# PowerPump_Circuitry.net
KiCad netlist of a schematic drawn in Altium Designer
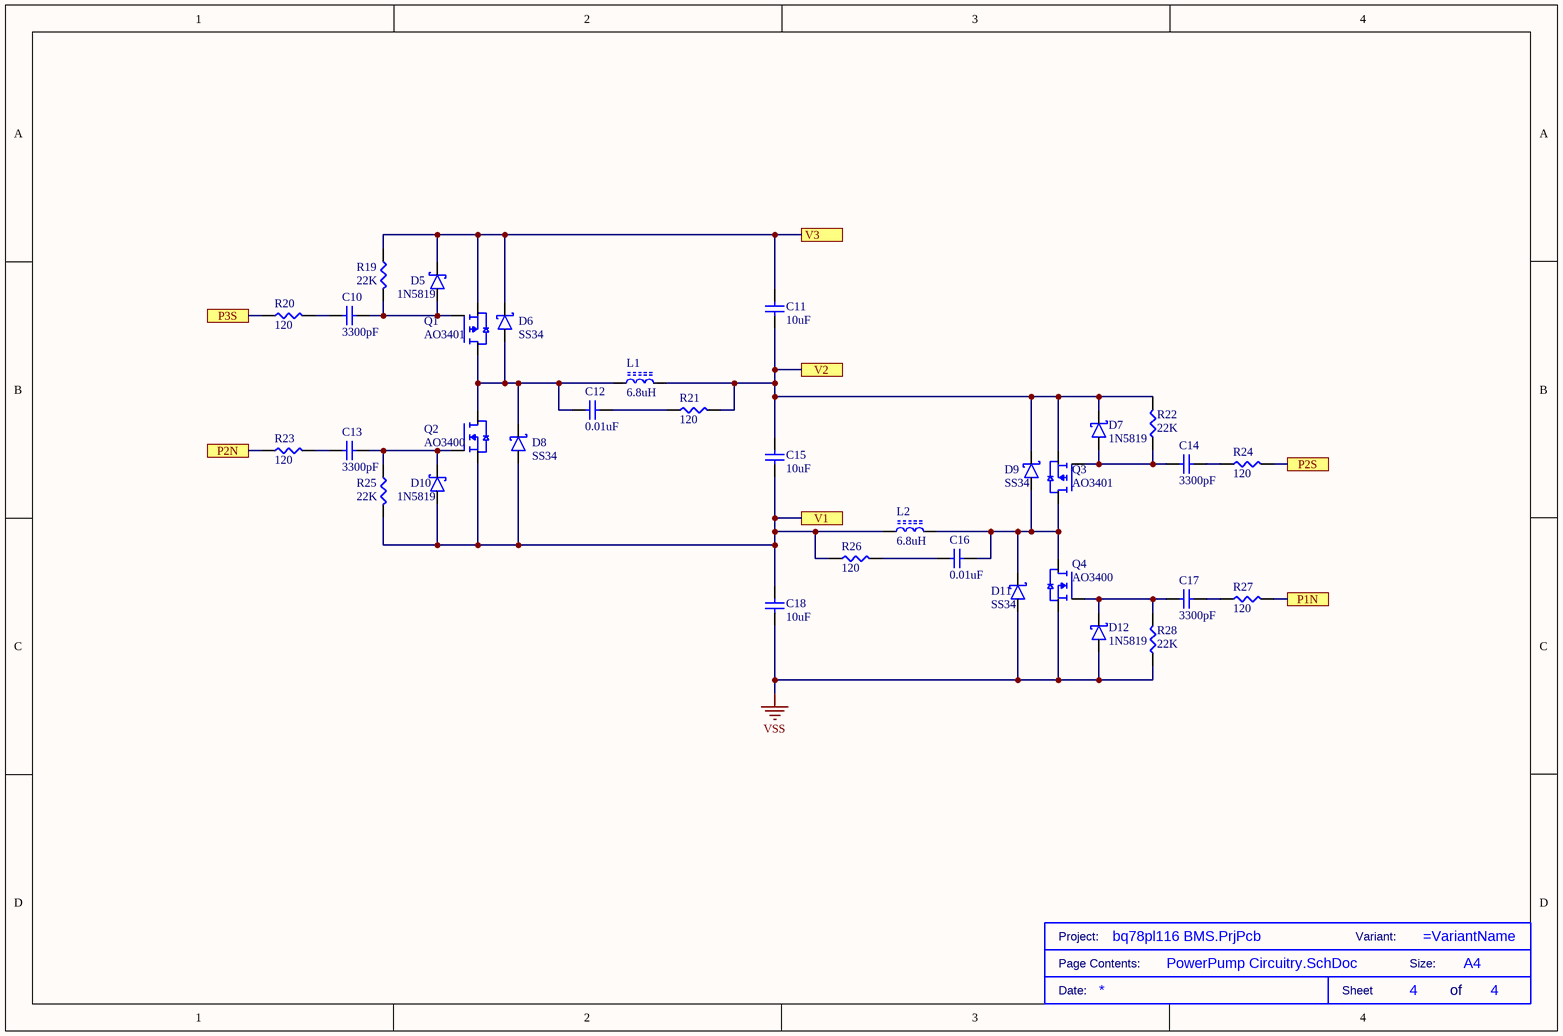
[diagram p0: PowerPump Circuitry.SchDoc]

(export (version "E")
  (design (tool "Eeschema 10.0.6"))
  (components
    (comp (ref "C10")
      (value "3300pF")
      (footprint "C0805")
      (description "Cap Ceramic 0.0033uF 50V X7R 10% SMD 0805 125C Paper T/R")
      (fields
        (field (name "MANUFACTURER") "KEMET")
        (field (name "MANUFACTURER PART NUMBER") "C0805C332K5RACTU")
      )
      (libsource (lib "MyLibrary") (part "CAP 0805 3300pF"))
    )
    (comp (ref "C11")
      (value "10uF")
      (footprint "C0805")
      (description "Cap Ceramic 10uF 10V X5R 10% SMD 0805 85C Plastic T/R")
      (fields
        (field (name "MANUFACTURER") "KEMET")
        (field (name "MANUFACTURER PART NUMBER") "C0805L106K8PACTU")
      )
      (libsource (lib "MyLibrary") (part "CAP 0805 10uF"))
    )
    (comp (ref "C12")
      (value "0.01uF")
      (footprint "C0805")
      (description "Cap Ceramic 0.01uF 16V X7R 10% SMD 0805 125°C Paper T/R")
      (fields
        (field (name "MANUFACTURER") "KEMET")
        (field (name "MANUFACTURER PART NUMBER") "C0805C103K4RACTU")
      )
      (libsource (lib "MyLibrary") (part "CAP 0805 0.01uF"))
    )
    (comp (ref "C13")
      (value "3300pF")
      (footprint "C0805")
      (description "Cap Ceramic 0.0033uF 50V X7R 10% SMD 0805 125C Paper T/R")
      (fields
        (field (name "MANUFACTURER") "KEMET")
        (field (name "MANUFACTURER PART NUMBER") "C0805C332K5RACTU")
      )
      (libsource (lib "MyLibrary") (part "CAP 0805 3300pF"))
    )
    (comp (ref "C14")
      (value "3300pF")
      (footprint "C0805")
      (description "Cap Ceramic 0.0033uF 50V X7R 10% SMD 0805 125C Paper T/R")
      (fields
        (field (name "MANUFACTURER") "KEMET")
        (field (name "MANUFACTURER PART NUMBER") "C0805C332K5RACTU")
      )
      (libsource (lib "MyLibrary") (part "CAP 0805 3300pF"))
    )
    (comp (ref "C15")
      (value "10uF")
      (footprint "C0805")
      (description "Cap Ceramic 10uF 10V X5R 10% SMD 0805 85C Plastic T/R")
      (fields
        (field (name "MANUFACTURER") "KEMET")
        (field (name "MANUFACTURER PART NUMBER") "C0805L106K8PACTU")
      )
      (libsource (lib "MyLibrary") (part "CAP 0805 10uF"))
    )
    (comp (ref "C16")
      (value "0.01uF")
      (footprint "C0805")
      (description "Cap Ceramic 0.01uF 16V X7R 10% SMD 0805 125°C Paper T/R")
      (fields
        (field (name "MANUFACTURER") "KEMET")
        (field (name "MANUFACTURER PART NUMBER") "C0805C103K4RACTU")
      )
      (libsource (lib "MyLibrary") (part "CAP 0805 0.01uF"))
    )
    (comp (ref "C17")
      (value "3300pF")
      (footprint "C0805")
      (description "Cap Ceramic 0.0033uF 50V X7R 10% SMD 0805 125C Paper T/R")
      (fields
        (field (name "MANUFACTURER") "KEMET")
        (field (name "MANUFACTURER PART NUMBER") "C0805C332K5RACTU")
      )
      (libsource (lib "MyLibrary") (part "CAP 0805 3300pF"))
    )
    (comp (ref "C18")
      (value "10uF")
      (footprint "C0805")
      (description "Cap Ceramic 10uF 10V X5R 10% SMD 0805 85C Plastic T/R")
      (fields
        (field (name "MANUFACTURER") "KEMET")
        (field (name "MANUFACTURER PART NUMBER") "C0805L106K8PACTU")
      )
      (libsource (lib "MyLibrary") (part "CAP 0805 10uF"))
    )
    (comp (ref "D5")
      (value "1N5819")
      (footprint "SOD123")
      (description "VR=40V IF=1A 60pF P=450mW")
      (fields (field (name "MANUFACTURER") "Diodes") (field (name "MANUFACTURER PART NUMBER") "1N5819HW-7-F"))
      (libsource (lib "MyLibrary") (part "1N5819HW-7-F"))
    )
    (comp (ref "D6")
      (value "SS34")
      (footprint "DO-214AA-SMB")
      (description "Diode Schottky 3A 40V Smb")
      (fields (field (name "MANUFACTURER") "Comchip") (field (name "MANUFACTURER PART NUMBER") "SS34B-HF"))
      (libsource (lib "MyLibrary") (part "SS34"))
    )
    (comp (ref "D7")
      (value "1N5819")
      (footprint "SOD123")
      (description "VR=40V IF=1A 60pF P=450mW")
      (fields (field (name "MANUFACTURER") "Diodes") (field (name "MANUFACTURER PART NUMBER") "1N5819HW-7-F"))
      (libsource (lib "MyLibrary") (part "1N5819HW-7-F"))
    )
    (comp (ref "D8")
      (value "SS34")
      (footprint "DO-214AA-SMB")
      (description "Diode Schottky 3A 40V Smb")
      (fields (field (name "MANUFACTURER") "Comchip") (field (name "MANUFACTURER PART NUMBER") "SS34B-HF"))
      (libsource (lib "MyLibrary") (part "SS34"))
    )
    (comp (ref "D9")
      (value "SS34")
      (footprint "DO-214AA-SMB")
      (description "Diode Schottky 3A 40V Smb")
      (fields (field (name "MANUFACTURER") "Comchip") (field (name "MANUFACTURER PART NUMBER") "SS34B-HF"))
      (libsource (lib "MyLibrary") (part "SS34"))
    )
    (comp (ref "D10")
      (value "1N5819")
      (footprint "SOD123")
      (description "VR=40V IF=1A 60pF P=450mW")
      (fields (field (name "MANUFACTURER") "Diodes") (field (name "MANUFACTURER PART NUMBER") "1N5819HW-7-F"))
      (libsource (lib "MyLibrary") (part "1N5819HW-7-F"))
    )
    (comp (ref "D11")
      (value "SS34")
      (footprint "DO-214AA-SMB")
      (description "Diode Schottky 3A 40V Smb")
      (fields (field (name "MANUFACTURER") "Comchip") (field (name "MANUFACTURER PART NUMBER") "SS34B-HF"))
      (libsource (lib "MyLibrary") (part "SS34"))
    )
    (comp (ref "D12")
      (value "1N5819")
      (footprint "SOD123")
      (description "VR=40V IF=1A 60pF P=450mW")
      (fields (field (name "MANUFACTURER") "Diodes") (field (name "MANUFACTURER PART NUMBER") "1N5819HW-7-F"))
      (libsource (lib "MyLibrary") (part "1N5819HW-7-F"))
    )
    (comp (ref "L1")
      (value "6.8uH")
      (footprint "CDRH5D28R")
      (description "Ind Power 6.8uH 25% Ferrite Drum Core T/R")
      (fields
        (field (name "MANUFACTURER") "Sumida")
        (field (name "MANUFACTURER PART NUMBER") "CDRH5D28RHPNP-6R8NC")
      )
      (libsource (lib "MyLibrary") (part "CDRH5D28RHPNP-6R8NC"))
    )
    (comp (ref "L2")
      (value "6.8uH")
      (footprint "CDRH5D28R")
      (description "Ind Power 6.8uH 25% Ferrite Drum Core T/R")
      (fields
        (field (name "MANUFACTURER") "Sumida")
        (field (name "MANUFACTURER PART NUMBER") "CDRH5D28RHPNP-6R8NC")
      )
      (libsource (lib "MyLibrary") (part "CDRH5D28RHPNP-6R8NC"))
    )
    (comp (ref "Q1")
      (value "AO3401")
      (footprint "SOT-23")
      (description "Trans Mosfet P-ch 30V 4A 3-PIN SOT-23 T/r")
      (fields
        (field (name "MANUFACTURER") "Alpha & Omega Semiconductor")
        (field (name "MANUFACTURER PART NUMBER") "AO3401A")
      )
      (libsource (lib "MyLibrary") (part "AO3401"))
    )
    (comp (ref "Q2")
      (value "AO3400")
      (footprint "SOT-23")
      (description "Trans MOSFET N-CH 30V 5.7A 3-Pin SOT-23")
      (fields
        (field (name "MANUFACTURER") "Alpha & Omega Semiconductor")
        (field (name "MANUFACTURER PART NUMBER") "AO3400A")
      )
      (libsource (lib "MyLibrary") (part "AO3400"))
    )
    (comp (ref "Q3")
      (value "AO3401")
      (footprint "SOT-23")
      (description "Trans Mosfet P-ch 30V 4A 3-PIN SOT-23 T/r")
      (fields
        (field (name "MANUFACTURER") "Alpha & Omega Semiconductor")
        (field (name "MANUFACTURER PART NUMBER") "AO3401A")
      )
      (libsource (lib "MyLibrary") (part "AO3401"))
    )
    (comp (ref "Q4")
      (value "AO3400")
      (footprint "SOT-23")
      (description "Trans MOSFET N-CH 30V 5.7A 3-Pin SOT-23")
      (fields
        (field (name "MANUFACTURER") "Alpha & Omega Semiconductor")
        (field (name "MANUFACTURER PART NUMBER") "AO3400A")
      )
      (libsource (lib "MyLibrary") (part "AO3400"))
    )
    (comp (ref "R19")
      (value "22K")
      (footprint "R0805")
      (description "CRCW Series 0805 0.125 W 22 KOhm ±5 % ±200 ppm/K SMT Thick Film Chip Resistor")
      (fields
        (field (name "MANUFACTURER") "Vishay")
        (field (name "MANUFACTURER PART NUMBER") "CRCW080522K0JNEAC")
      )
      (libsource (lib "MyLibrary") (part "RES 0805 22K"))
    )
    (comp (ref "R20")
      (value "120")
      (footprint "R0805")
      (description "Res 120 Ohm 5% 1/8W 0805")
      (fields
        (field (name "MANUFACTURER") "Vishay")
        (field (name "MANUFACTURER PART NUMBER") "CRCW0805120RJNEAC")
      )
      (libsource (lib "MyLibrary") (part "RES 0805 120"))
    )
    (comp (ref "R21")
      (value "120")
      (footprint "R0805")
      (description "Res 120 Ohm 5% 1/8W 0805")
      (fields
        (field (name "MANUFACTURER") "Vishay")
        (field (name "MANUFACTURER PART NUMBER") "CRCW0805120RJNEAC")
      )
      (libsource (lib "MyLibrary") (part "RES 0805 120"))
    )
    (comp (ref "R22")
      (value "22K")
      (footprint "R0805")
      (description "CRCW Series 0805 0.125 W 22 KOhm ±5 % ±200 ppm/K SMT Thick Film Chip Resistor")
      (fields
        (field (name "MANUFACTURER") "Vishay")
        (field (name "MANUFACTURER PART NUMBER") "CRCW080522K0JNEAC")
      )
      (libsource (lib "MyLibrary") (part "RES 0805 22K"))
    )
    (comp (ref "R23")
      (value "120")
      (footprint "R0805")
      (description "Res 120 Ohm 5% 1/8W 0805")
      (fields
        (field (name "MANUFACTURER") "Vishay")
        (field (name "MANUFACTURER PART NUMBER") "CRCW0805120RJNEAC")
      )
      (libsource (lib "MyLibrary") (part "RES 0805 120"))
    )
    (comp (ref "R24")
      (value "120")
      (footprint "R0805")
      (description "Res 120 Ohm 5% 1/8W 0805")
      (fields
        (field (name "MANUFACTURER") "Vishay")
        (field (name "MANUFACTURER PART NUMBER") "CRCW0805120RJNEAC")
      )
      (libsource (lib "MyLibrary") (part "RES 0805 120"))
    )
    (comp (ref "R25")
      (value "22K")
      (footprint "R0805")
      (description "CRCW Series 0805 0.125 W 22 KOhm ±5 % ±200 ppm/K SMT Thick Film Chip Resistor")
      (fields
        (field (name "MANUFACTURER") "Vishay")
        (field (name "MANUFACTURER PART NUMBER") "CRCW080522K0JNEAC")
      )
      (libsource (lib "MyLibrary") (part "RES 0805 22K"))
    )
    (comp (ref "R26")
      (value "120")
      (footprint "R0805")
      (description "Res 120 Ohm 5% 1/8W 0805")
      (fields
        (field (name "MANUFACTURER") "Vishay")
        (field (name "MANUFACTURER PART NUMBER") "CRCW0805120RJNEAC")
      )
      (libsource (lib "MyLibrary") (part "RES 0805 120"))
    )
    (comp (ref "R27")
      (value "120")
      (footprint "R0805")
      (description "Res 120 Ohm 5% 1/8W 0805")
      (fields
        (field (name "MANUFACTURER") "Vishay")
        (field (name "MANUFACTURER PART NUMBER") "CRCW0805120RJNEAC")
      )
      (libsource (lib "MyLibrary") (part "RES 0805 120"))
    )
    (comp (ref "R28")
      (value "22K")
      (footprint "R0805")
      (description "CRCW Series 0805 0.125 W 22 KOhm ±5 % ±200 ppm/K SMT Thick Film Chip Resistor")
      (fields
        (field (name "MANUFACTURER") "Vishay")
        (field (name "MANUFACTURER PART NUMBER") "CRCW080522K0JNEAC")
      )
      (libsource (lib "MyLibrary") (part "RES 0805 22K"))
    )
  )
  (nets
    (net (code "1") (name "/P1N") (class "Default")
      (node (ref "R27") (pin "2") (pinfunction "2_2") (pintype "passive"))
    )
    (net (code "2") (name "/P2N") (class "Default")
      (node (ref "R23") (pin "1") (pinfunction "1_1") (pintype "passive"))
    )
    (net (code "3") (name "/P2S") (class "Default")
      (node (ref "R24") (pin "2") (pinfunction "2_2") (pintype "passive"))
    )
    (net (code "4") (name "/P3S") (class "Default")
      (node (ref "R20") (pin "1") (pinfunction "1_1") (pintype "passive"))
    )
    (net (code "5") (name "/V1") (class "Default")
      (node (ref "C15") (pin "2") (pinfunction "2_2") (pintype "passive"))
      (node (ref "C18") (pin "1") (pinfunction "1_1") (pintype "passive"))
      (node (ref "D10") (pin "1") (pinfunction "A_1") (pintype "passive"))
      (node (ref "D8") (pin "1") (pinfunction "A_1") (pintype "passive"))
      (node (ref "L2") (pin "1") (pinfunction "1_1") (pintype "passive"))
      (node (ref "Q2") (pin "2") (pinfunction "S_2") (pintype "passive"))
      (node (ref "R25") (pin "1") (pinfunction "1_1") (pintype "passive"))
      (node (ref "R26") (pin "1") (pinfunction "1_1") (pintype "passive"))
    )
    (net (code "6") (name "/V2") (class "Default")
      (node (ref "C11") (pin "2") (pinfunction "2_2") (pintype "passive"))
      (node (ref "C15") (pin "1") (pinfunction "1_1") (pintype "passive"))
      (node (ref "D7") (pin "2") (pinfunction "K_2") (pintype "passive"))
      (node (ref "D9") (pin "2") (pinfunction "K_2") (pintype "passive"))
      (node (ref "L1") (pin "2") (pinfunction "2_2") (pintype "passive"))
      (node (ref "Q3") (pin "2") (pinfunction "S_2") (pintype "passive"))
      (node (ref "R21") (pin "2") (pinfunction "2_2") (pintype "passive"))
      (node (ref "R22") (pin "2") (pinfunction "2_2") (pintype "passive"))
    )
    (net (code "7") (name "/V3") (class "Default")
      (node (ref "C11") (pin "1") (pinfunction "1_1") (pintype "passive"))
      (node (ref "D5") (pin "2") (pinfunction "K_2") (pintype "passive"))
      (node (ref "D6") (pin "2") (pinfunction "K_2") (pintype "passive"))
      (node (ref "Q1") (pin "2") (pinfunction "S_2") (pintype "passive"))
      (node (ref "R19") (pin "2") (pinfunction "2_2") (pintype "passive"))
    )
    (net (code "8") (name "Net-(C10-Pad1)") (class "Default")
      (node (ref "C10") (pin "1") (pinfunction "1_1") (pintype "passive"))
      (node (ref "R20") (pin "2") (pinfunction "2_2") (pintype "passive"))
    )
    (net (code "9") (name "Net-(C12-Pad2)") (class "Default")
      (node (ref "C12") (pin "2") (pinfunction "2_2") (pintype "passive"))
      (node (ref "R21") (pin "1") (pinfunction "1_1") (pintype "passive"))
    )
    (net (code "10") (name "Net-(C13-Pad1)") (class "Default")
      (node (ref "C13") (pin "1") (pinfunction "1_1") (pintype "passive"))
      (node (ref "R23") (pin "2") (pinfunction "2_2") (pintype "passive"))
    )
    (net (code "11") (name "Net-(C14-Pad2)") (class "Default")
      (node (ref "C14") (pin "2") (pinfunction "2_2") (pintype "passive"))
      (node (ref "R24") (pin "1") (pinfunction "1_1") (pintype "passive"))
    )
    (net (code "12") (name "Net-(C16-Pad1)") (class "Default")
      (node (ref "C16") (pin "1") (pinfunction "1_1") (pintype "passive"))
      (node (ref "R26") (pin "2") (pinfunction "2_2") (pintype "passive"))
    )
    (net (code "13") (name "Net-(C17-Pad2)") (class "Default")
      (node (ref "C17") (pin "2") (pinfunction "2_2") (pintype "passive"))
      (node (ref "R27") (pin "1") (pinfunction "1_1") (pintype "passive"))
    )
    (net (code "14") (name "Net-(D5-A)") (class "Default")
      (node (ref "C10") (pin "2") (pinfunction "2_2") (pintype "passive"))
      (node (ref "D5") (pin "1") (pinfunction "A_1") (pintype "passive"))
      (node (ref "Q1") (pin "1") (pinfunction "G_1") (pintype "passive"))
      (node (ref "R19") (pin "1") (pinfunction "1_1") (pintype "passive"))
    )
    (net (code "15") (name "Net-(D6-A)") (class "Default")
      (node (ref "C12") (pin "1") (pinfunction "1_1") (pintype "passive"))
      (node (ref "D6") (pin "1") (pinfunction "A_1") (pintype "passive"))
      (node (ref "D8") (pin "2") (pinfunction "K_2") (pintype "passive"))
      (node (ref "L1") (pin "1") (pinfunction "1_1") (pintype "passive"))
      (node (ref "Q1") (pin "3") (pinfunction "D_3") (pintype "passive"))
      (node (ref "Q2") (pin "3") (pinfunction "D_3") (pintype "passive"))
    )
    (net (code "16") (name "Net-(D7-A)") (class "Default")
      (node (ref "C14") (pin "1") (pinfunction "1_1") (pintype "passive"))
      (node (ref "D7") (pin "1") (pinfunction "A_1") (pintype "passive"))
      (node (ref "Q3") (pin "1") (pinfunction "G_1") (pintype "passive"))
      (node (ref "R22") (pin "1") (pinfunction "1_1") (pintype "passive"))
    )
    (net (code "17") (name "Net-(D10-K)") (class "Default")
      (node (ref "C13") (pin "2") (pinfunction "2_2") (pintype "passive"))
      (node (ref "D10") (pin "2") (pinfunction "K_2") (pintype "passive"))
      (node (ref "Q2") (pin "1") (pinfunction "G_1") (pintype "passive"))
      (node (ref "R25") (pin "2") (pinfunction "2_2") (pintype "passive"))
    )
    (net (code "18") (name "Net-(D11-K)") (class "Default")
      (node (ref "C16") (pin "2") (pinfunction "2_2") (pintype "passive"))
      (node (ref "D11") (pin "2") (pinfunction "K_2") (pintype "passive"))
      (node (ref "D9") (pin "1") (pinfunction "A_1") (pintype "passive"))
      (node (ref "L2") (pin "2") (pinfunction "2_2") (pintype "passive"))
      (node (ref "Q3") (pin "3") (pinfunction "D_3") (pintype "passive"))
      (node (ref "Q4") (pin "3") (pinfunction "D_3") (pintype "passive"))
    )
    (net (code "19") (name "Net-(D12-K)") (class "Default")
      (node (ref "C17") (pin "1") (pinfunction "1_1") (pintype "passive"))
      (node (ref "D12") (pin "2") (pinfunction "K_2") (pintype "passive"))
      (node (ref "Q4") (pin "1") (pinfunction "G_1") (pintype "passive"))
      (node (ref "R28") (pin "2") (pinfunction "2_2") (pintype "passive"))
    )
    (net (code "20") (name "VSS") (class "Default")
      (node (ref "C18") (pin "2") (pinfunction "2_2") (pintype "passive"))
      (node (ref "D11") (pin "1") (pinfunction "A_1") (pintype "passive"))
      (node (ref "D12") (pin "1") (pinfunction "A_1") (pintype "passive"))
      (node (ref "Q4") (pin "2") (pinfunction "S_2") (pintype "passive"))
      (node (ref "R28") (pin "1") (pinfunction "1_1") (pintype "passive"))
    )
  )
)
